# Sheet1.net
KiCad netlist of a schematic drawn in Altium Designer
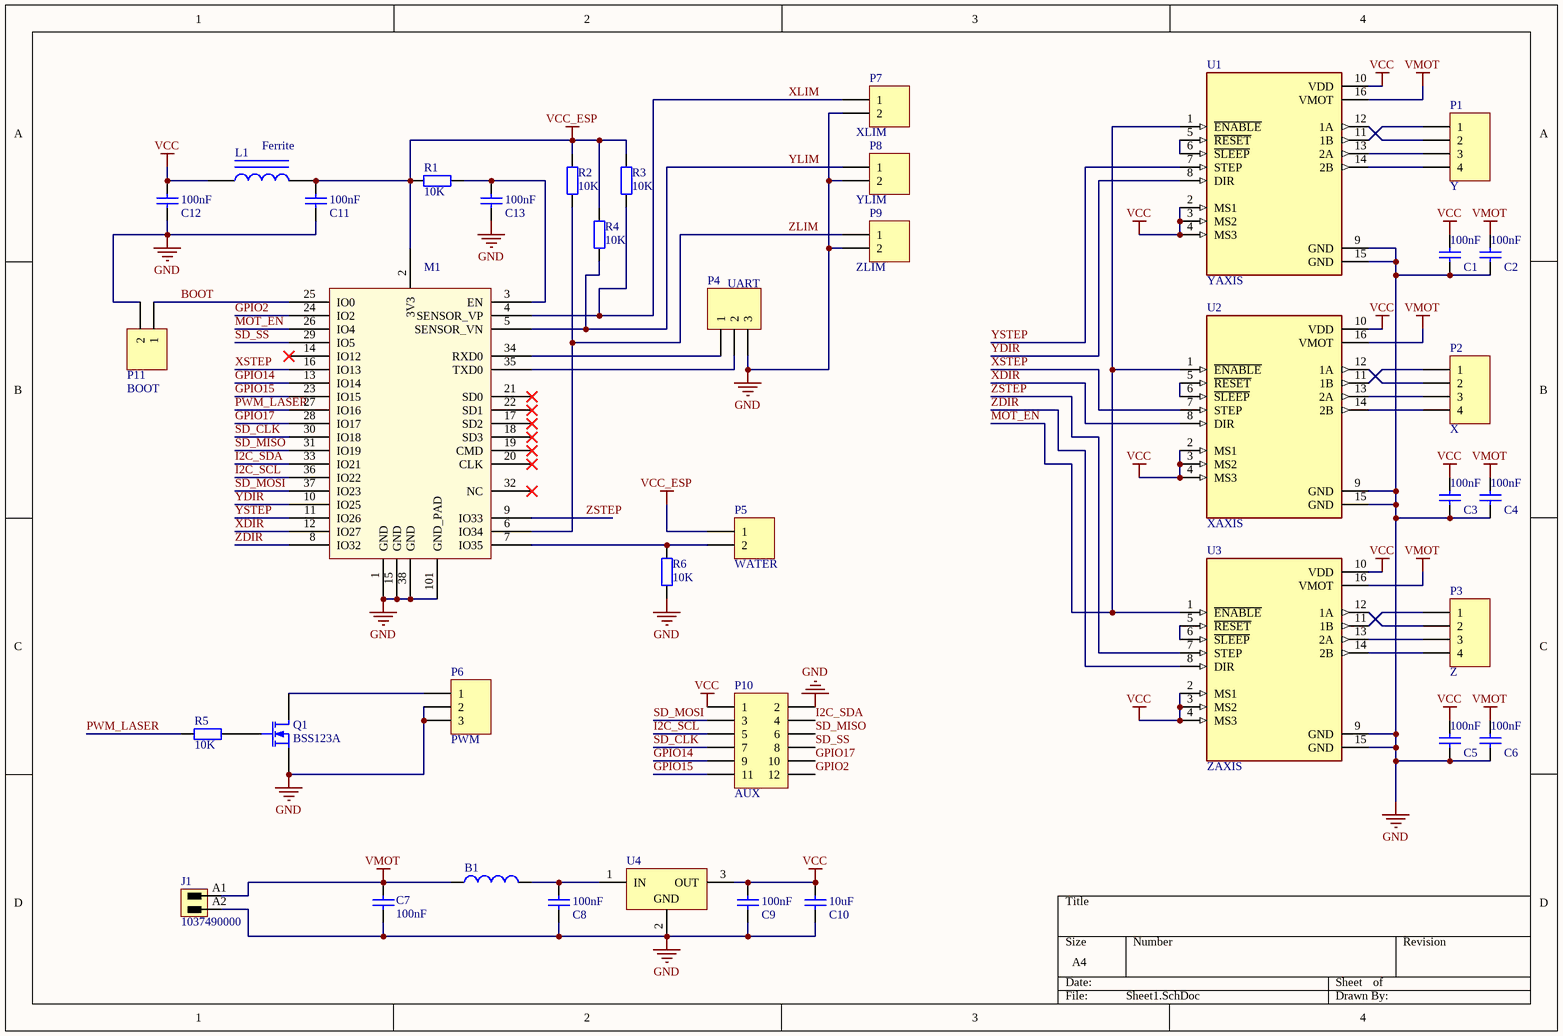
[diagram p0: Sheet1.SchDoc]

(export (version "E")
  (design (tool "Eeschema 10.0.6"))
  (components
    (comp (ref "B1")
      (value "Ferrite")
      (footprint "INDC3225N")
      (description "Inductor")
      (fields (field (name "MANUFACTURER") "Murata"))
      (libsource (lib "Miscellaneous Devices") (part "Inductor"))
    )
    (comp (ref "C1")
      (value "100nF")
      (footprint "0805")
      (description "Capacitor (Semiconductor SIM Model)")
      (fields (field (name "VOLTAGE") "50V") (field (name "MANUFACTURER") "Generic Components"))
      (libsource (lib "Miscellaneous Devices") (part "Cap Semi"))
    )
    (comp (ref "C2")
      (value "100nF")
      (footprint "0805")
      (description "Capacitor (Semiconductor SIM Model)")
      (fields (field (name "VOLTAGE") "50V") (field (name "MANUFACTURER") "Generic Components"))
      (libsource (lib "Miscellaneous Devices") (part "Cap Semi"))
    )
    (comp (ref "C3")
      (value "100nF")
      (footprint "0805")
      (description "Capacitor (Semiconductor SIM Model)")
      (fields (field (name "VOLTAGE") "50V") (field (name "MANUFACTURER") "Generic Components"))
      (libsource (lib "Miscellaneous Devices") (part "Cap Semi"))
    )
    (comp (ref "C4")
      (value "100nF")
      (footprint "0805")
      (description "Capacitor (Semiconductor SIM Model)")
      (fields (field (name "VOLTAGE") "50V") (field (name "MANUFACTURER") "Generic Components"))
      (libsource (lib "Miscellaneous Devices") (part "Cap Semi"))
    )
    (comp (ref "C5")
      (value "100nF")
      (footprint "0805")
      (description "Capacitor (Semiconductor SIM Model)")
      (fields (field (name "VOLTAGE") "50V") (field (name "MANUFACTURER") "Generic Components"))
      (libsource (lib "Miscellaneous Devices") (part "Cap Semi"))
    )
    (comp (ref "C6")
      (value "100nF")
      (footprint "0805")
      (description "Capacitor (Semiconductor SIM Model)")
      (fields (field (name "VOLTAGE") "50V") (field (name "MANUFACTURER") "Generic Components"))
      (libsource (lib "Miscellaneous Devices") (part "Cap Semi"))
    )
    (comp (ref "C7")
      (value "100nF")
      (footprint "0805")
      (description "Capacitor (Semiconductor SIM Model)")
      (fields (field (name "VOLTAGE") "50V") (field (name "MANUFACTURER") "Generic Components"))
      (libsource (lib "Miscellaneous Devices") (part "Cap Semi"))
    )
    (comp (ref "C8")
      (value "100nF")
      (footprint "0805")
      (description "Capacitor (Semiconductor SIM Model)")
      (fields (field (name "VOLTAGE") "50V") (field (name "MANUFACTURER") "Generic Components"))
      (libsource (lib "Miscellaneous Devices") (part "Cap Semi"))
    )
    (comp (ref "C9")
      (value "100nF")
      (footprint "0805")
      (description "Capacitor (Semiconductor SIM Model)")
      (fields (field (name "VOLTAGE") "50V") (field (name "MANUFACTURER") "Generic Components"))
      (libsource (lib "Miscellaneous Devices") (part "Cap Semi"))
    )
    (comp (ref "C10")
      (value "10uF")
      (footprint "1210")
      (description "Capacitor (Semiconductor SIM Model)")
      (fields (field (name "VOLTAGE") "25V") (field (name "MANUFACTURER") "Generic Components"))
      (libsource (lib "Miscellaneous Devices") (part "Cap Semi"))
    )
    (comp (ref "C11")
      (value "100nF")
      (footprint "0805")
      (description "Capacitor (Semiconductor SIM Model)")
      (fields (field (name "VOLTAGE") "50V") (field (name "MANUFACTURER") "Generic Components"))
      (libsource (lib "Miscellaneous Devices") (part "Cap Semi"))
    )
    (comp (ref "C12")
      (value "100nF")
      (footprint "0805")
      (description "Capacitor (Semiconductor SIM Model)")
      (fields (field (name "VOLTAGE") "50V") (field (name "MANUFACTURER") "Generic Components"))
      (libsource (lib "Miscellaneous Devices") (part "Cap Semi"))
    )
    (comp (ref "C13")
      (value "100nF")
      (footprint "0805")
      (description "Capacitor (Semiconductor SIM Model)")
      (fields (field (name "VOLTAGE") "50V") (field (name "MANUFACTURER") "Generic Components"))
      (libsource (lib "Miscellaneous Devices") (part "Cap Semi"))
    )
    (comp (ref "J1")
      (value "1037490000")
      (footprint "SC_3_81_270G_02")
      (description "OMNIMATE Signal - series BC/SC 3.81")
      (fields (field (name "MANUFACTURER") "Weidmueller"))
      (libsource (lib "Weidmueller_OMNIMATE_Signal") (part "1037490000"))
    )
    (comp (ref "L1")
      (value "Ferrite")
      (footprint "INDC2012N")
      (description "Magnetic-Core Inductor")
      (fields (field (name "MANUFACTURER") "Murata"))
      (libsource (lib "Miscellaneous Devices") (part "Inductor Iron"))
    )
    (comp (ref "M1")
      (value "ESP32S_Module")
      (footprint "ESP32S")
      (description "Esp-32S")
      (libsource (lib "ESP32S") (part "ESP32S_Module"))
    )
    (comp (ref "P1")
      (value "Y")
      (footprint "HDR1X4")
      (description "Header, 4-Pin")
      (fields (field (name "PUBLISHER") "Altium Limited"))
      (libsource (lib "Miscellaneous Connectors") (part "Header 4"))
    )
    (comp (ref "P2")
      (value "X")
      (footprint "HDR1X4")
      (description "Header, 4-Pin")
      (fields (field (name "PUBLISHER") "Altium Limited"))
      (libsource (lib "Miscellaneous Connectors") (part "Header 4"))
    )
    (comp (ref "P3")
      (value "Z")
      (footprint "HDR1X4")
      (description "Header, 4-Pin")
      (fields (field (name "PUBLISHER") "Altium Limited"))
      (libsource (lib "Miscellaneous Connectors") (part "Header 4"))
    )
    (comp (ref "P4")
      (value "UART")
      (footprint "HDR1X3")
      (description "Header, 3-Pin")
      (fields (field (name "PUBLISHER") "Altium Limited"))
      (libsource (lib "Miscellaneous Connectors") (part "Header 3"))
    )
    (comp (ref "P5")
      (value "WATER")
      (footprint "HDR1X2")
      (description "Header, 2-Pin")
      (fields (field (name "PUBLISHER") "Altium Limited"))
      (libsource (lib "Miscellaneous Connectors") (part "Header 2"))
    )
    (comp (ref "P6")
      (value "PWM")
      (footprint "HDR1X3")
      (description "Header, 3-Pin")
      (fields (field (name "PUBLISHER") "Altium Limited"))
      (libsource (lib "") (part "Header 3_1"))
    )
    (comp (ref "P7")
      (value "XLIM")
      (footprint "HDR1X2")
      (description "Header, 2-Pin")
      (fields (field (name "PUBLISHER") "Altium Limited"))
      (libsource (lib "Miscellaneous Connectors") (part "Header 2"))
    )
    (comp (ref "P8")
      (value "YLIM")
      (footprint "HDR1X2")
      (description "Header, 2-Pin")
      (fields (field (name "PUBLISHER") "Altium Limited"))
      (libsource (lib "Miscellaneous Connectors") (part "Header 2"))
    )
    (comp (ref "P9")
      (value "ZLIM")
      (footprint "HDR1X2")
      (description "Header, 2-Pin")
      (fields (field (name "PUBLISHER") "Altium Limited"))
      (libsource (lib "Miscellaneous Connectors") (part "Header 2"))
    )
    (comp (ref "P10")
      (value "AUX")
      (footprint "HDR2X6")
      (description "Header, 6-Pin, Dual row")
      (fields (field (name "PUBLISHER") "Altium Limited"))
      (libsource (lib "Miscellaneous Connectors") (part "Header 6X2"))
    )
    (comp (ref "P11")
      (value "BOOT")
      (footprint "HDR1X2")
      (description "Header, 2-Pin")
      (fields (field (name "PUBLISHER") "Altium Limited"))
      (libsource (lib "") (part "Header 2_1"))
    )
    (comp (ref "Q1")
      (value "BSS123A")
      (footprint "SOT23_M")
      (description "N-Channel Enhancement Mode Vertical DMOS FET")
      (fields (field (name "PUBLISHER") "Altium Limited"))
      (libsource (lib "Zetex Discrete MOSFET") (part "BSS123A"))
    )
    (comp (ref "R1")
      (value "10K")
      (footprint "0805")
      (description "Resistor")
      (fields (field (name "MANUFACTURER") "Generic Components") (field (name "Comment") "Res2"))
      (libsource (lib "") (part "Res2_1"))
    )
    (comp (ref "R2")
      (value "10K")
      (footprint "0805")
      (description "Resistor")
      (fields (field (name "MANUFACTURER") "Generic Components") (field (name "Comment") "Res2"))
      (libsource (lib "Miscellaneous Devices") (part "Res2"))
    )
    (comp (ref "R3")
      (value "10K")
      (footprint "0805")
      (description "Resistor")
      (fields (field (name "MANUFACTURER") "Generic Components") (field (name "Comment") "Res2"))
      (libsource (lib "Miscellaneous Devices") (part "Res2"))
    )
    (comp (ref "R4")
      (value "10K")
      (footprint "0805")
      (description "Resistor")
      (fields (field (name "MANUFACTURER") "Generic Components") (field (name "Comment") "Res2"))
      (libsource (lib "Miscellaneous Devices") (part "Res2"))
    )
    (comp (ref "R5")
      (value "10K")
      (footprint "0805")
      (description "Resistor")
      (fields (field (name "MANUFACTURER") "Generic Components") (field (name "Comment") "Res2"))
      (libsource (lib "") (part "Res2_2"))
    )
    (comp (ref "R6")
      (value "10K")
      (footprint "0805")
      (description "Resistor")
      (fields (field (name "MANUFACTURER") "Generic Components") (field (name "Comment") "Res2"))
      (libsource (lib "Miscellaneous Devices") (part "Res2"))
    )
    (comp (ref "U1")
      (value "YAXIS")
      (footprint "MODULE_A4988_STEPPER_MOTOR_DRIVER_CARRIER")
      (description "Stepper Motor Driver")
      (fields (field (name "MP") "A4988 STEPPER MOTOR DRIVER CARRIER") (field (name "MF") "Pololu"))
      (libsource (lib "A4988_STEPPER_MOTOR_DRIVER_CARRIER") (part "A4988_STEPPER_MOTOR_DRIVER_CARRIER"))
    )
    (comp (ref "U2")
      (value "XAXIS")
      (footprint "MODULE_A4988_STEPPER_MOTOR_DRIVER_CARRIER")
      (description "Stepper Motor Driver")
      (fields (field (name "MP") "A4988 STEPPER MOTOR DRIVER CARRIER") (field (name "MF") "Pololu"))
      (libsource (lib "A4988_STEPPER_MOTOR_DRIVER_CARRIER") (part "A4988_STEPPER_MOTOR_DRIVER_CARRIER"))
    )
    (comp (ref "U3")
      (value "ZAXIS")
      (footprint "MODULE_A4988_STEPPER_MOTOR_DRIVER_CARRIER")
      (description "Stepper Motor Driver")
      (fields (field (name "MP") "A4988 STEPPER MOTOR DRIVER CARRIER") (field (name "MF") "Pololu"))
      (libsource (lib "A4988_STEPPER_MOTOR_DRIVER_CARRIER") (part "A4988_STEPPER_MOTOR_DRIVER_CARRIER"))
    )
    (comp (ref "U4")
      (value "3V3REG")
      (footprint "TRS1-24xx")
      (description "Switching Regulator,18-32Vin,3.3Vout 1A")
      (libsource (lib "Medios") (part "TSR1-2433"))
    )
  )
  (nets
    (net (code "1") (name "/BOOT") (class "Default")
      (node (ref "M1") (pin "25") (pinfunction "IO0_25") (pintype "passive"))
      (node (ref "P11") (pin "1") (pinfunction "1_1") (pintype "passive"))
    )
    (net (code "2") (name "/GPIO2") (class "Default")
      (node (ref "M1") (pin "24") (pinfunction "IO2_24") (pintype "passive"))
      (node (ref "P10") (pin "12") (pinfunction "12_12") (pintype "passive"))
    )
    (net (code "3") (name "/GPIO14") (class "Default")
      (node (ref "M1") (pin "13") (pinfunction "IO14_13") (pintype "passive"))
      (node (ref "P10") (pin "9") (pinfunction "9_9") (pintype "passive"))
    )
    (net (code "4") (name "/GPIO15") (class "Default")
      (node (ref "M1") (pin "23") (pinfunction "IO15_23") (pintype "passive"))
      (node (ref "P10") (pin "11") (pinfunction "11_11") (pintype "passive"))
    )
    (net (code "5") (name "/GPIO17") (class "Default")
      (node (ref "M1") (pin "28") (pinfunction "IO17_28") (pintype "passive"))
      (node (ref "P10") (pin "10") (pinfunction "10_10") (pintype "passive"))
    )
    (net (code "6") (name "/I2C_SCL") (class "Default")
      (node (ref "M1") (pin "36") (pinfunction "IO22_36") (pintype "passive"))
      (node (ref "P10") (pin "5") (pinfunction "5_5") (pintype "passive"))
    )
    (net (code "7") (name "/I2C_SDA") (class "Default")
      (node (ref "M1") (pin "33") (pinfunction "IO21_33") (pintype "passive"))
      (node (ref "P10") (pin "4") (pinfunction "4_4") (pintype "passive"))
    )
    (net (code "8") (name "/MOT_EN") (class "Default")
      (node (ref "M1") (pin "26") (pinfunction "IO4_26") (pintype "passive"))
      (node (ref "U1") (pin "1") (pinfunction "~{ENABLE}_1") (pintype "input"))
      (node (ref "U2") (pin "1") (pinfunction "~{ENABLE}_1") (pintype "input"))
      (node (ref "U3") (pin "1") (pinfunction "~{ENABLE}_1") (pintype "input"))
    )
    (net (code "9") (name "/PWM_LASER") (class "Default")
      (node (ref "M1") (pin "27") (pinfunction "IO16_27") (pintype "passive"))
      (node (ref "R5") (pin "1") (pinfunction "1_1") (pintype "passive"))
    )
    (net (code "10") (name "/SD_CLK") (class "Default")
      (node (ref "M1") (pin "30") (pinfunction "IO18_30") (pintype "passive"))
      (node (ref "P10") (pin "7") (pinfunction "7_7") (pintype "passive"))
    )
    (net (code "11") (name "/SD_MISO") (class "Default")
      (node (ref "M1") (pin "31") (pinfunction "IO19_31") (pintype "passive"))
      (node (ref "P10") (pin "6") (pinfunction "6_6") (pintype "passive"))
    )
    (net (code "12") (name "/SD_MOSI") (class "Default")
      (node (ref "M1") (pin "37") (pinfunction "IO23_37") (pintype "passive"))
      (node (ref "P10") (pin "3") (pinfunction "3_3") (pintype "passive"))
    )
    (net (code "13") (name "/SD_SS") (class "Default")
      (node (ref "M1") (pin "29") (pinfunction "IO5_29") (pintype "passive"))
      (node (ref "P10") (pin "8") (pinfunction "8_8") (pintype "passive"))
    )
    (net (code "14") (name "/XDIR") (class "Default")
      (node (ref "M1") (pin "12") (pinfunction "IO27_12") (pintype "passive"))
      (node (ref "U2") (pin "8") (pinfunction "DIR_8") (pintype "input"))
    )
    (net (code "15") (name "/XLIM") (class "Default")
      (node (ref "M1") (pin "4") (pinfunction "SENSOR_VP_4") (pintype "passive"))
      (node (ref "P7") (pin "1") (pinfunction "1_1") (pintype "passive"))
      (node (ref "R3") (pin "2") (pinfunction "2_2") (pintype "passive"))
    )
    (net (code "16") (name "/XSTEP") (class "Default")
      (node (ref "M1") (pin "16") (pinfunction "IO13_16") (pintype "passive"))
      (node (ref "U2") (pin "7") (pinfunction "STEP_7") (pintype "input"))
    )
    (net (code "17") (name "/YDIR") (class "Default")
      (node (ref "M1") (pin "10") (pinfunction "IO25_10") (pintype "passive"))
      (node (ref "U1") (pin "8") (pinfunction "DIR_8") (pintype "input"))
    )
    (net (code "18") (name "/YLIM") (class "Default")
      (node (ref "M1") (pin "5") (pinfunction "SENSOR_VN_5") (pintype "passive"))
      (node (ref "P8") (pin "1") (pinfunction "1_1") (pintype "passive"))
      (node (ref "R4") (pin "2") (pinfunction "2_2") (pintype "passive"))
    )
    (net (code "19") (name "/YSTEP") (class "Default")
      (node (ref "M1") (pin "11") (pinfunction "IO26_11") (pintype "passive"))
      (node (ref "U1") (pin "7") (pinfunction "STEP_7") (pintype "input"))
    )
    (net (code "20") (name "/ZDIR") (class "Default")
      (node (ref "M1") (pin "8") (pinfunction "IO32_8") (pintype "passive"))
      (node (ref "U3") (pin "8") (pinfunction "DIR_8") (pintype "input"))
    )
    (net (code "21") (name "/ZLIM") (class "Default")
      (node (ref "M1") (pin "6") (pinfunction "IO34_6") (pintype "passive"))
      (node (ref "P9") (pin "1") (pinfunction "1_1") (pintype "passive"))
      (node (ref "R2") (pin "2") (pinfunction "2_2") (pintype "passive"))
    )
    (net (code "22") (name "/ZSTEP") (class "Default")
      (node (ref "M1") (pin "9") (pinfunction "IO33_9") (pintype "passive"))
      (node (ref "U3") (pin "7") (pinfunction "STEP_7") (pintype "input"))
    )
    (net (code "23") (name "GND") (class "Default")
      (node (ref "C1") (pin "2") (pinfunction "2_2") (pintype "passive"))
      (node (ref "C10") (pin "2") (pinfunction "2_2") (pintype "passive"))
      (node (ref "C11") (pin "2") (pinfunction "2_2") (pintype "passive"))
      (node (ref "C12") (pin "2") (pinfunction "2_2") (pintype "passive"))
      (node (ref "C13") (pin "2") (pinfunction "2_2") (pintype "passive"))
      (node (ref "C2") (pin "2") (pinfunction "2_2") (pintype "passive"))
      (node (ref "C3") (pin "2") (pinfunction "2_2") (pintype "passive"))
      (node (ref "C4") (pin "2") (pinfunction "2_2") (pintype "passive"))
      (node (ref "C5") (pin "2") (pinfunction "2_2") (pintype "passive"))
      (node (ref "C6") (pin "2") (pinfunction "2_2") (pintype "passive"))
      (node (ref "C7") (pin "1") (pinfunction "1_1") (pintype "passive"))
      (node (ref "C8") (pin "2") (pinfunction "2_2") (pintype "passive"))
      (node (ref "C9") (pin "2") (pinfunction "2_2") (pintype "passive"))
      (node (ref "J1") (pin "A2") (pinfunction "A2_A2") (pintype "passive"))
      (node (ref "M1") (pin "1") (pinfunction "GND_1") (pintype "power_in"))
      (node (ref "M1") (pin "101") (pinfunction "GND_PAD_101") (pintype "power_in"))
      (node (ref "M1") (pin "15") (pinfunction "GND_15") (pintype "power_in"))
      (node (ref "M1") (pin "38") (pinfunction "GND_38") (pintype "power_in"))
      (node (ref "P10") (pin "2") (pinfunction "2_2") (pintype "passive"))
      (node (ref "P11") (pin "2") (pinfunction "2_2") (pintype "passive"))
      (node (ref "P4") (pin "3") (pinfunction "3_3") (pintype "passive"))
      (node (ref "P6") (pin "2") (pinfunction "2_2") (pintype "passive"))
      (node (ref "P6") (pin "3") (pinfunction "3_3") (pintype "passive"))
      (node (ref "P7") (pin "2") (pinfunction "2_2") (pintype "passive"))
      (node (ref "P8") (pin "2") (pinfunction "2_2") (pintype "passive"))
      (node (ref "P9") (pin "2") (pinfunction "2_2") (pintype "passive"))
      (node (ref "Q1") (pin "2") (pinfunction "S_2") (pintype "passive"))
      (node (ref "R6") (pin "2") (pinfunction "2_2") (pintype "passive"))
      (node (ref "U1") (pin "15") (pinfunction "GND_15") (pintype "power_in"))
      (node (ref "U1") (pin "9") (pinfunction "GND_9") (pintype "power_in"))
      (node (ref "U2") (pin "15") (pinfunction "GND_15") (pintype "power_in"))
      (node (ref "U2") (pin "9") (pinfunction "GND_9") (pintype "power_in"))
      (node (ref "U3") (pin "15") (pinfunction "GND_15") (pintype "power_in"))
      (node (ref "U3") (pin "9") (pinfunction "GND_9") (pintype "power_in"))
      (node (ref "U4") (pin "2") (pinfunction "GND_2") (pintype "power_in"))
    )
    (net (code "24") (name "Net-(M1-EN)") (class "Default")
      (node (ref "C13") (pin "1") (pinfunction "1_1") (pintype "passive"))
      (node (ref "M1") (pin "3") (pinfunction "EN_3") (pintype "power_in"))
      (node (ref "R1") (pin "1") (pinfunction "1_1") (pintype "passive"))
    )
    (net (code "25") (name "Net-(M1-IO35)") (class "Default")
      (node (ref "M1") (pin "7") (pinfunction "IO35_7") (pintype "passive"))
      (node (ref "P5") (pin "2") (pinfunction "2_2") (pintype "passive"))
      (node (ref "R6") (pin "1") (pinfunction "1_1") (pintype "passive"))
    )
    (net (code "26") (name "Net-(M1-RXD0)") (class "Default")
      (node (ref "M1") (pin "34") (pinfunction "RXD0_34") (pintype "passive"))
      (node (ref "P4") (pin "1") (pinfunction "1_1") (pintype "passive"))
    )
    (net (code "27") (name "Net-(M1-TXD0)") (class "Default")
      (node (ref "M1") (pin "35") (pinfunction "TXD0_35") (pintype "passive"))
      (node (ref "P4") (pin "2") (pinfunction "2_2") (pintype "passive"))
    )
    (net (code "28") (name "Net-(Q1-D)") (class "Default")
      (node (ref "P6") (pin "1") (pinfunction "1_1") (pintype "passive"))
      (node (ref "Q1") (pin "1") (pinfunction "D_1") (pintype "passive"))
    )
    (net (code "29") (name "Net-(Q1-G)") (class "Default")
      (node (ref "Q1") (pin "3") (pinfunction "G_3") (pintype "passive"))
      (node (ref "R5") (pin "2") (pinfunction "2_2") (pintype "passive"))
    )
    (net (code "30") (name "Net-(U1-1A)") (class "Default")
      (node (ref "P1") (pin "2") (pinfunction "2_2") (pintype "passive"))
      (node (ref "U1") (pin "12") (pinfunction "1A_12") (pintype "output"))
    )
    (net (code "31") (name "Net-(U1-1B)") (class "Default")
      (node (ref "P1") (pin "1") (pinfunction "1_1") (pintype "passive"))
      (node (ref "U1") (pin "11") (pinfunction "1B_11") (pintype "output"))
    )
    (net (code "32") (name "Net-(U1-2A)") (class "Default")
      (node (ref "P1") (pin "3") (pinfunction "3_3") (pintype "passive"))
      (node (ref "U1") (pin "13") (pinfunction "2A_13") (pintype "output"))
    )
    (net (code "33") (name "Net-(U1-2B)") (class "Default")
      (node (ref "P1") (pin "4") (pinfunction "4_4") (pintype "passive"))
      (node (ref "U1") (pin "14") (pinfunction "2B_14") (pintype "output"))
    )
    (net (code "34") (name "Net-(U1-~{RESET})") (class "Default")
      (node (ref "U1") (pin "5") (pinfunction "~{RESET}_5") (pintype "input"))
      (node (ref "U1") (pin "6") (pinfunction "~{SLEEP}_6") (pintype "input"))
    )
    (net (code "35") (name "Net-(U2-1A)") (class "Default")
      (node (ref "P2") (pin "2") (pinfunction "2_2") (pintype "passive"))
      (node (ref "U2") (pin "12") (pinfunction "1A_12") (pintype "output"))
    )
    (net (code "36") (name "Net-(U2-1B)") (class "Default")
      (node (ref "P2") (pin "1") (pinfunction "1_1") (pintype "passive"))
      (node (ref "U2") (pin "11") (pinfunction "1B_11") (pintype "output"))
    )
    (net (code "37") (name "Net-(U2-2A)") (class "Default")
      (node (ref "P2") (pin "3") (pinfunction "3_3") (pintype "passive"))
      (node (ref "U2") (pin "13") (pinfunction "2A_13") (pintype "output"))
    )
    (net (code "38") (name "Net-(U2-2B)") (class "Default")
      (node (ref "P2") (pin "4") (pinfunction "4_4") (pintype "passive"))
      (node (ref "U2") (pin "14") (pinfunction "2B_14") (pintype "output"))
    )
    (net (code "39") (name "Net-(U2-~{RESET})") (class "Default")
      (node (ref "U2") (pin "5") (pinfunction "~{RESET}_5") (pintype "input"))
      (node (ref "U2") (pin "6") (pinfunction "~{SLEEP}_6") (pintype "input"))
    )
    (net (code "40") (name "Net-(U3-1A)") (class "Default")
      (node (ref "P3") (pin "2") (pinfunction "2_2") (pintype "passive"))
      (node (ref "U3") (pin "12") (pinfunction "1A_12") (pintype "output"))
    )
    (net (code "41") (name "Net-(U3-1B)") (class "Default")
      (node (ref "P3") (pin "1") (pinfunction "1_1") (pintype "passive"))
      (node (ref "U3") (pin "11") (pinfunction "1B_11") (pintype "output"))
    )
    (net (code "42") (name "Net-(U3-2A)") (class "Default")
      (node (ref "P3") (pin "3") (pinfunction "3_3") (pintype "passive"))
      (node (ref "U3") (pin "13") (pinfunction "2A_13") (pintype "output"))
    )
    (net (code "43") (name "Net-(U3-2B)") (class "Default")
      (node (ref "P3") (pin "4") (pinfunction "4_4") (pintype "passive"))
      (node (ref "U3") (pin "14") (pinfunction "2B_14") (pintype "output"))
    )
    (net (code "44") (name "Net-(U3-~{RESET})") (class "Default")
      (node (ref "U3") (pin "5") (pinfunction "~{RESET}_5") (pintype "input"))
      (node (ref "U3") (pin "6") (pinfunction "~{SLEEP}_6") (pintype "input"))
    )
    (net (code "45") (name "Net-(U4-IN)") (class "Default")
      (node (ref "B1") (pin "2") (pinfunction "2_2") (pintype "passive"))
      (node (ref "C8") (pin "1") (pinfunction "1_1") (pintype "passive"))
      (node (ref "U4") (pin "1") (pinfunction "IN_1") (pintype "power_in"))
    )
    (net (code "46") (name "VCC") (class "Default")
      (node (ref "C1") (pin "1") (pinfunction "1_1") (pintype "passive"))
      (node (ref "C10") (pin "1") (pinfunction "1_1") (pintype "passive"))
      (node (ref "C12") (pin "1") (pinfunction "1_1") (pintype "passive"))
      (node (ref "C3") (pin "1") (pinfunction "1_1") (pintype "passive"))
      (node (ref "C5") (pin "1") (pinfunction "1_1") (pintype "passive"))
      (node (ref "C9") (pin "1") (pinfunction "1_1") (pintype "passive"))
      (node (ref "L1") (pin "1") (pinfunction "1_1") (pintype "passive"))
      (node (ref "P10") (pin "1") (pinfunction "1_1") (pintype "passive"))
      (node (ref "U1") (pin "10") (pinfunction "VDD_10") (pintype "power_in"))
      (node (ref "U1") (pin "2") (pinfunction "MS1_2") (pintype "input"))
      (node (ref "U1") (pin "3") (pinfunction "MS2_3") (pintype "input"))
      (node (ref "U1") (pin "4") (pinfunction "MS3_4") (pintype "input"))
      (node (ref "U2") (pin "10") (pinfunction "VDD_10") (pintype "power_in"))
      (node (ref "U2") (pin "2") (pinfunction "MS1_2") (pintype "input"))
      (node (ref "U2") (pin "3") (pinfunction "MS2_3") (pintype "input"))
      (node (ref "U2") (pin "4") (pinfunction "MS3_4") (pintype "input"))
      (node (ref "U3") (pin "10") (pinfunction "VDD_10") (pintype "power_in"))
      (node (ref "U3") (pin "2") (pinfunction "MS1_2") (pintype "input"))
      (node (ref "U3") (pin "3") (pinfunction "MS2_3") (pintype "input"))
      (node (ref "U3") (pin "4") (pinfunction "MS3_4") (pintype "input"))
      (node (ref "U4") (pin "3") (pinfunction "OUT_3") (pintype "power_in"))
    )
    (net (code "47") (name "VCC_ESP") (class "Default")
      (node (ref "C11") (pin "1") (pinfunction "1_1") (pintype "passive"))
      (node (ref "L1") (pin "2") (pinfunction "2_2") (pintype "passive"))
      (node (ref "M1") (pin "2") (pinfunction "3V3_2") (pintype "power_in"))
      (node (ref "P5") (pin "1") (pinfunction "1_1") (pintype "passive"))
      (node (ref "R1") (pin "2") (pinfunction "2_2") (pintype "passive"))
      (node (ref "R2") (pin "1") (pinfunction "1_1") (pintype "passive"))
      (node (ref "R3") (pin "1") (pinfunction "1_1") (pintype "passive"))
      (node (ref "R4") (pin "1") (pinfunction "1_1") (pintype "passive"))
    )
    (net (code "48") (name "VMOT") (class "Default")
      (node (ref "B1") (pin "1") (pinfunction "1_1") (pintype "passive"))
      (node (ref "C2") (pin "1") (pinfunction "1_1") (pintype "passive"))
      (node (ref "C4") (pin "1") (pinfunction "1_1") (pintype "passive"))
      (node (ref "C6") (pin "1") (pinfunction "1_1") (pintype "passive"))
      (node (ref "C7") (pin "2") (pinfunction "2_2") (pintype "passive"))
      (node (ref "J1") (pin "A1") (pinfunction "A1_A1") (pintype "passive"))
      (node (ref "U1") (pin "16") (pinfunction "VMOT_16") (pintype "power_in"))
      (node (ref "U2") (pin "16") (pinfunction "VMOT_16") (pintype "power_in"))
      (node (ref "U3") (pin "16") (pinfunction "VMOT_16") (pintype "power_in"))
    )
    (net (code "49") (name "unconnected-(M1-CLK-Pad20)") (class "Default")
      (node (ref "M1") (pin "20") (pinfunction "CLK_20") (pintype "passive+no_connect"))
    )
    (net (code "50") (name "unconnected-(M1-CMD-Pad19)") (class "Default")
      (node (ref "M1") (pin "19") (pinfunction "CMD_19") (pintype "passive+no_connect"))
    )
    (net (code "51") (name "unconnected-(M1-IO12-Pad14)") (class "Default")
      (node (ref "M1") (pin "14") (pinfunction "IO12_14") (pintype "passive+no_connect"))
    )
    (net (code "52") (name "unconnected-(M1-NC-Pad32)") (class "Default")
      (node (ref "M1") (pin "32") (pinfunction "NC_32") (pintype "passive+no_connect"))
    )
    (net (code "53") (name "unconnected-(M1-SD0-Pad21)") (class "Default")
      (node (ref "M1") (pin "21") (pinfunction "SD0_21") (pintype "passive+no_connect"))
    )
    (net (code "54") (name "unconnected-(M1-SD1-Pad22)") (class "Default")
      (node (ref "M1") (pin "22") (pinfunction "SD1_22") (pintype "passive+no_connect"))
    )
    (net (code "55") (name "unconnected-(M1-SD2-Pad17)") (class "Default")
      (node (ref "M1") (pin "17") (pinfunction "SD2_17") (pintype "passive+no_connect"))
    )
    (net (code "56") (name "unconnected-(M1-SD3-Pad18)") (class "Default")
      (node (ref "M1") (pin "18") (pinfunction "SD3_18") (pintype "passive+no_connect"))
    )
  )
)
